# RF.net
KiCad netlist of a schematic drawn in Altium Designer
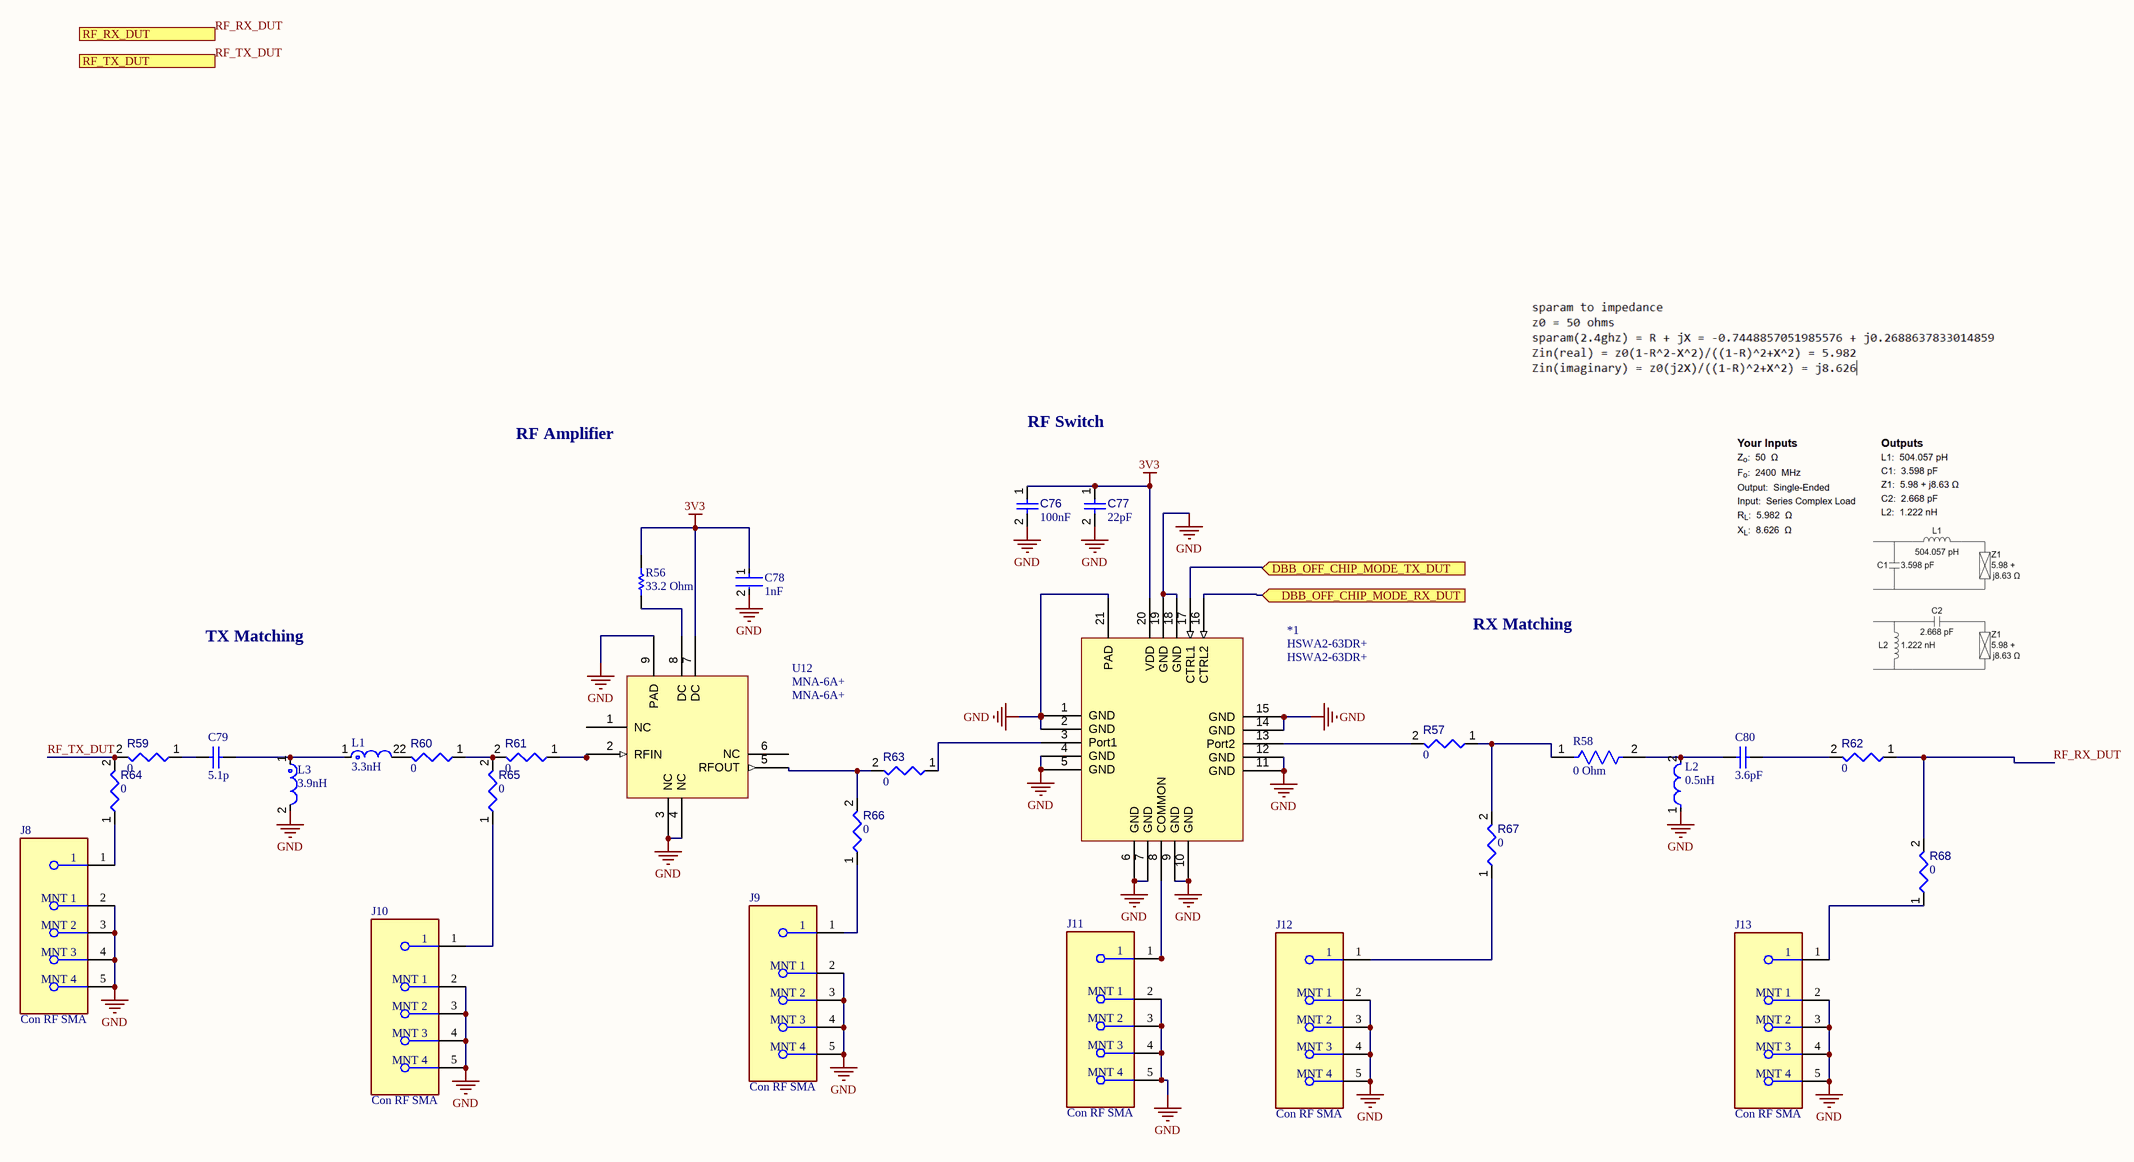
[diagram p0: RF.SchDoc]

(export (version "E")
  (design (tool "Eeschema 10.0.6"))
  (components
    (comp (ref "*1")
      (value "HSWA2-63DR+")
      (footprint "HSWA2-63DR+-Footprint-1")
      (description "Absorptive SPDT, SMT Solid State")
      (fields (field (name "U10") "HSWA2-63DR+") (field (name "MANUFACTURER") "Mini-Circuits"))
      (libsource (lib "EE194 Fall2022") (part "HSWA2-63DR+"))
    )
    (comp (ref "C76")
      (value "100nF")
      (footprint "CAPC1005X56X25LL10T15")
      (description "Chip Capacitor, 0.1 uF, +/- 5%, 16 V, 0402 (1005 Metric)")
      (fields (field (name "TOLERANCE") "5%") (field (name "Comment") "0.1uF"))
      (libsource (lib "EE194 Fall2022") (part "CAP-NP-2"))
    )
    (comp (ref "C77")
      (value "22pF")
      (footprint "CAPC0402(1005)60_L")
      (description "Chip Capacitor, 22pF +/-10%, 50V, 0402, Thickness 0.6 mm")
      (fields (field (name "TOLERANCE") "10%"))
      (libsource (lib "EE194 Fall2022") (part "CAP-NP-2"))
    )
    (comp (ref "C78")
      (value "1nF")
      (footprint "FP-CL10-IPC_C")
      (description "Cap Ceramic 1nF 50V X7R ±10% Pad SMD 0603 +125°C T/R")
      (fields (field (name "VOLTAGE") "50V") (field (name "TOLERANCE") "10%"))
      (libsource (lib "Altium Content Vault") (part "b4654b650e69147ec39a6b967a45e02"))
    )
    (comp (ref "C79")
      (value "5.1p")
      (footprint "CAPC1608X90X35NL15T15")
      (fields
        (field (name "PART NUMBER") "06031A5R1CAT2A")
        (field (name "MANUFACTURER") "AVX Interconnect / Elco")
      )
      (libsource (lib "Altium Content Vault") (part "CAP"))
    )
    (comp (ref "C80")
      (value "3.6pF")
      (footprint "CAPC1608X74X38LL10T13")
      (fields
        (field (name "MANUFACTURER") "AVX Interconnect / Elco")
        (field (name "PART NUMBER") "ML03V13R6BAT2A")
      )
      (libsource (lib "Altium Content Vault") (part "CAP"))
    )
    (comp (ref "J8")
      (value "Con RF SMA")
      (footprint "FP-RF2-04A-T-00-50-G-MFG")
      (description "CONN SMA JACK STR 50 OHM PCB")
      (libsource (lib "Altium Content Vault") (part "c65b8a639cdaef1819ea20b5466f8fa"))
    )
    (comp (ref "J9")
      (value "Con RF SMA")
      (footprint "FP-RF2-04A-T-00-50-G-MFG")
      (description "CONN SMA JACK STR 50 OHM PCB")
      (libsource (lib "Altium Content Vault") (part "c65b8a639cdaef1819ea20b5466f8fa"))
    )
    (comp (ref "J10")
      (value "Con RF SMA")
      (footprint "FP-RF2-04A-T-00-50-G-MFG")
      (description "CONN SMA JACK STR 50 OHM PCB")
      (libsource (lib "Altium Content Vault") (part "c65b8a639cdaef1819ea20b5466f8fa"))
    )
    (comp (ref "J11")
      (value "Con RF SMA")
      (footprint "FP-RF2-04A-T-00-50-G-MFG")
      (description "CONN SMA JACK STR 50 OHM PCB")
      (libsource (lib "Altium Content Vault") (part "c65b8a639cdaef1819ea20b5466f8fa"))
    )
    (comp (ref "J12")
      (value "Con RF SMA")
      (footprint "FP-RF2-04A-T-00-50-G-MFG")
      (description "CONN SMA JACK STR 50 OHM PCB")
      (libsource (lib "Altium Content Vault") (part "c65b8a639cdaef1819ea20b5466f8fa"))
    )
    (comp (ref "J13")
      (value "Con RF SMA")
      (footprint "FP-RF2-04A-T-00-50-G-MFG")
      (description "CONN SMA JACK STR 50 OHM PCB")
      (libsource (lib "Altium Content Vault") (part "c65b8a639cdaef1819ea20b5466f8fa"))
    )
    (comp (ref "L1")
      (value "3.3nH")
      (footprint "FP-LQG18HH_00-MFG")
      (description "Multilayer type RF Inductor 3.3nH ±0.3nH 0.12Ω 1000mA 0603")
      (libsource (lib "Altium Content Vault") (part "4cc4b267dca4c8e51f7102f422741d8"))
    )
    (comp (ref "L2")
      (value "0.5nH")
      (footprint "FP-LQW18AN_00-MFG")
      (description "Wire Wound RF Inductor 5.6nH ±0.5nH 750mA 0.082Ω 0603 (1608)")
      (libsource (lib "Altium Content Vault") (part "725321dda6339637d4d059423bc1c3c"))
    )
    (comp (ref "L3")
      (value "3.9nH")
      (footprint "FP-LQG18HH_00-MFG")
      (description "Multilayer type RF Inductor 3.9nH ±0.3nH 0.15Ω 900mA 0603")
      (libsource (lib "Altium Content Vault") (part "4cc4b267dca4c8e51f7102f422741d8"))
    )
    (comp (ref "R56")
      (value "33.2 Ohm")
      (footprint "RESC1608X55X25NL10T15")
      (fields (field (name "MANUFACTURER") "Yageo") (field (name "PART NUMBER") "RC0603FR-0733R2L"))
      (libsource (lib "Altium Content Vault") (part "RES"))
    )
    (comp (ref "R57")
      (value "0")
      (footprint "RESC0603(1608)_L")
      (description "Jumper 0603 (1608 Metric)")
      (fields (field (name "Comment") "0R3J"))
      (libsource (lib "EE194 Fall2022") (part "0R3J"))
    )
    (comp (ref "R58")
      (value "0 Ohm")
      (footprint "FP-CRCW0603-C-IPC_B")
      (description "RES 0 OHM JUMPER 1/10W 0603")
      (libsource (lib "Altium Content Vault") (part "1029c3af85768c4190bb7ad29bc67b5"))
    )
    (comp (ref "R59")
      (value "0")
      (footprint "RESC0603(1608)_L")
      (description "Jumper 0603 (1608 Metric)")
      (fields (field (name "Comment") "0R3J"))
      (libsource (lib "EE194 Fall2022") (part "0R3J"))
    )
    (comp (ref "R60")
      (value "0")
      (footprint "RESC0603(1608)_L")
      (description "Jumper 0603 (1608 Metric)")
      (fields (field (name "Comment") "0R3J"))
      (libsource (lib "EE194 Fall2022") (part "0R3J"))
    )
    (comp (ref "R61")
      (value "0")
      (footprint "RESC0603(1608)_L")
      (description "Jumper 0603 (1608 Metric)")
      (fields (field (name "Comment") "0R3J"))
      (libsource (lib "EE194 Fall2022") (part "0R3J"))
    )
    (comp (ref "R62")
      (value "0")
      (footprint "RESC0603(1608)_L")
      (description "Jumper 0603 (1608 Metric)")
      (fields (field (name "Comment") "0R3J"))
      (libsource (lib "EE194 Fall2022") (part "0R3J"))
    )
    (comp (ref "R63")
      (value "0")
      (footprint "RESC0603(1608)_L")
      (description "Jumper 0603 (1608 Metric)")
      (fields (field (name "Comment") "0R3J"))
      (libsource (lib "EE194 Fall2022") (part "0R3J"))
    )
    (comp (ref "R64")
      (value "0")
      (footprint "RESC0603(1608)_L")
      (description "Jumper 0603 (1608 Metric)")
      (fields (field (name "Comment") "0R3J"))
      (libsource (lib "EE194 Fall2022") (part "0R3J"))
    )
    (comp (ref "R65")
      (value "0")
      (footprint "RESC0603(1608)_L")
      (description "Jumper 0603 (1608 Metric)")
      (fields (field (name "Comment") "0R3J"))
      (libsource (lib "EE194 Fall2022") (part "0R3J"))
    )
    (comp (ref "R66")
      (value "0")
      (footprint "RESC0603(1608)_L")
      (description "Jumper 0603 (1608 Metric)")
      (fields (field (name "Comment") "0R3J"))
      (libsource (lib "EE194 Fall2022") (part "0R3J"))
    )
    (comp (ref "R67")
      (value "0")
      (footprint "RESC0603(1608)_L")
      (description "Jumper 0603 (1608 Metric)")
      (fields (field (name "Comment") "0R3J"))
      (libsource (lib "EE194 Fall2022") (part "0R3J"))
    )
    (comp (ref "R68")
      (value "0")
      (footprint "RESC0603(1608)_L")
      (description "Jumper 0603 (1608 Metric)")
      (fields (field (name "Comment") "0R3J"))
      (libsource (lib "EE194 Fall2022") (part "0R3J"))
    )
    (comp (ref "U12")
      (value "MNA-6A+")
      (footprint "MNA-6A+-Footprint-1")
      (description "RF Amp Single MMIC Amp 2.5GHz 5V 8-Pin Case DQ-849 T/R")
      (fields (field (name "U11") "MNA-6A+") (field (name "MANUFACTURER") "Mini-Circuits"))
      (libsource (lib "EE194 Fall2022") (part "MNA-6A+"))
    )
  )
  (nets
    (net (code "1") (name "/DBB_OFF_CHIP_MODE_RX_DUT") (class "Default")
      (node (ref "*1") (pin "16") (pinfunction "CTRL2_16") (pintype "input"))
    )
    (net (code "2") (name "/DBB_OFF_CHIP_MODE_TX_DUT") (class "Default")
      (node (ref "*1") (pin "17") (pinfunction "CTRL1_17") (pintype "input"))
    )
    (net (code "3") (name "/RF_RX_DUT") (class "Default")
      (node (ref "R62") (pin "1") (pinfunction "1_1") (pintype "passive"))
      (node (ref "R68") (pin "2") (pinfunction "2_2") (pintype "passive"))
    )
    (net (code "4") (name "/RF_TX_DUT") (class "Default")
      (node (ref "R59") (pin "2") (pinfunction "2_2") (pintype "passive"))
      (node (ref "R64") (pin "2") (pinfunction "2_2") (pintype "passive"))
    )
    (net (code "5") (name "3V3") (class "Default")
      (node (ref "*1") (pin "20") (pinfunction "VDD_20") (pintype "passive"))
      (node (ref "C76") (pin "1") (pinfunction "1_1") (pintype "passive"))
      (node (ref "C77") (pin "1") (pinfunction "1_1") (pintype "passive"))
      (node (ref "C78") (pin "1") (pinfunction "1_1") (pintype "passive"))
      (node (ref "R56") (pin "2") (pinfunction "2_2") (pintype "passive"))
      (node (ref "U12") (pin "7") (pinfunction "DC_7") (pintype "passive"))
    )
    (net (code "6") (name "GND") (class "Default")
      (node (ref "*1") (pin "1") (pinfunction "GND_1") (pintype "passive"))
      (node (ref "*1") (pin "10") (pinfunction "GND_10") (pintype "passive"))
      (node (ref "*1") (pin "11") (pinfunction "GND_11") (pintype "passive"))
      (node (ref "*1") (pin "12") (pinfunction "GND_12") (pintype "passive"))
      (node (ref "*1") (pin "14") (pinfunction "GND_14") (pintype "passive"))
      (node (ref "*1") (pin "15") (pinfunction "GND_15") (pintype "passive"))
      (node (ref "*1") (pin "18") (pinfunction "GND_18") (pintype "passive"))
      (node (ref "*1") (pin "19") (pinfunction "GND_19") (pintype "passive"))
      (node (ref "*1") (pin "2") (pinfunction "GND_2") (pintype "passive"))
      (node (ref "*1") (pin "21") (pinfunction "PAD_21") (pintype "passive"))
      (node (ref "*1") (pin "4") (pinfunction "GND_4") (pintype "passive"))
      (node (ref "*1") (pin "5") (pinfunction "GND_5") (pintype "passive"))
      (node (ref "*1") (pin "6") (pinfunction "GND_6") (pintype "passive"))
      (node (ref "*1") (pin "7") (pinfunction "GND_7") (pintype "passive"))
      (node (ref "*1") (pin "9") (pinfunction "GND_9") (pintype "passive"))
      (node (ref "C76") (pin "2") (pinfunction "2_2") (pintype "passive"))
      (node (ref "C77") (pin "2") (pinfunction "2_2") (pintype "passive"))
      (node (ref "C78") (pin "2") (pinfunction "2_2") (pintype "passive"))
      (node (ref "J10") (pin "2") (pinfunction "MNT_1_2") (pintype "passive"))
      (node (ref "J10") (pin "3") (pinfunction "MNT_2_3") (pintype "passive"))
      (node (ref "J10") (pin "4") (pinfunction "MNT_3_4") (pintype "passive"))
      (node (ref "J10") (pin "5") (pinfunction "MNT_4_5") (pintype "passive"))
      (node (ref "J11") (pin "2") (pinfunction "MNT_1_2") (pintype "passive"))
      (node (ref "J11") (pin "3") (pinfunction "MNT_2_3") (pintype "passive"))
      (node (ref "J11") (pin "4") (pinfunction "MNT_3_4") (pintype "passive"))
      (node (ref "J11") (pin "5") (pinfunction "MNT_4_5") (pintype "passive"))
      (node (ref "J12") (pin "2") (pinfunction "MNT_1_2") (pintype "passive"))
      (node (ref "J12") (pin "3") (pinfunction "MNT_2_3") (pintype "passive"))
      (node (ref "J12") (pin "4") (pinfunction "MNT_3_4") (pintype "passive"))
      (node (ref "J12") (pin "5") (pinfunction "MNT_4_5") (pintype "passive"))
      (node (ref "J13") (pin "2") (pinfunction "MNT_1_2") (pintype "passive"))
      (node (ref "J13") (pin "3") (pinfunction "MNT_2_3") (pintype "passive"))
      (node (ref "J13") (pin "4") (pinfunction "MNT_3_4") (pintype "passive"))
      (node (ref "J13") (pin "5") (pinfunction "MNT_4_5") (pintype "passive"))
      (node (ref "J8") (pin "2") (pinfunction "MNT_1_2") (pintype "passive"))
      (node (ref "J8") (pin "3") (pinfunction "MNT_2_3") (pintype "passive"))
      (node (ref "J8") (pin "4") (pinfunction "MNT_3_4") (pintype "passive"))
      (node (ref "J8") (pin "5") (pinfunction "MNT_4_5") (pintype "passive"))
      (node (ref "J9") (pin "2") (pinfunction "MNT_1_2") (pintype "passive"))
      (node (ref "J9") (pin "3") (pinfunction "MNT_2_3") (pintype "passive"))
      (node (ref "J9") (pin "4") (pinfunction "MNT_3_4") (pintype "passive"))
      (node (ref "J9") (pin "5") (pinfunction "MNT_4_5") (pintype "passive"))
      (node (ref "L2") (pin "1") (pinfunction "1_1") (pintype "passive"))
      (node (ref "L3") (pin "2") (pinfunction "2_2") (pintype "passive"))
      (node (ref "U12") (pin "3") (pinfunction "NC_3") (pintype "passive"))
      (node (ref "U12") (pin "4") (pinfunction "NC_4") (pintype "passive"))
      (node (ref "U12") (pin "9") (pinfunction "PAD_9") (pintype "passive"))
    )
    (net (code "7") (name "Net-(*1-COMMON)") (class "Default")
      (node (ref "*1") (pin "8") (pinfunction "COMMON_8") (pintype "passive"))
      (node (ref "J11") (pin "1") (pinfunction "1_1") (pintype "passive"))
    )
    (net (code "8") (name "Net-(*1-Port1)") (class "Default")
      (node (ref "*1") (pin "3") (pinfunction "Port1_3") (pintype "passive"))
      (node (ref "R63") (pin "1") (pinfunction "1_1") (pintype "passive"))
    )
    (net (code "9") (name "Net-(*1-Port2)") (class "Default")
      (node (ref "*1") (pin "13") (pinfunction "Port2_13") (pintype "passive"))
      (node (ref "R57") (pin "2") (pinfunction "2_2") (pintype "passive"))
    )
    (net (code "10") (name "Net-(C79-Pad1)") (class "Default")
      (node (ref "C79") (pin "1") (pinfunction "1_1") (pintype "passive"))
      (node (ref "R59") (pin "1") (pinfunction "1_1") (pintype "passive"))
    )
    (net (code "11") (name "Net-(C79-Pad2)") (class "Default")
      (node (ref "C79") (pin "2") (pinfunction "2_2") (pintype "passive"))
      (node (ref "L1") (pin "1") (pinfunction "1_1") (pintype "passive"))
      (node (ref "L3") (pin "1") (pinfunction "1_1") (pintype "passive"))
    )
    (net (code "12") (name "Net-(C80-Pad1)") (class "Default")
      (node (ref "C80") (pin "1") (pinfunction "1_1") (pintype "passive"))
      (node (ref "L2") (pin "2") (pinfunction "2_2") (pintype "passive"))
      (node (ref "R58") (pin "2") (pinfunction "2_2") (pintype "passive"))
    )
    (net (code "13") (name "Net-(C80-Pad2)") (class "Default")
      (node (ref "C80") (pin "2") (pinfunction "2_2") (pintype "passive"))
      (node (ref "R62") (pin "2") (pinfunction "2_2") (pintype "passive"))
    )
    (net (code "14") (name "Net-(J8-Pad1)") (class "Default")
      (node (ref "J8") (pin "1") (pinfunction "1_1") (pintype "passive"))
      (node (ref "R64") (pin "1") (pinfunction "1_1") (pintype "passive"))
    )
    (net (code "15") (name "Net-(J9-Pad1)") (class "Default")
      (node (ref "J9") (pin "1") (pinfunction "1_1") (pintype "passive"))
      (node (ref "R66") (pin "1") (pinfunction "1_1") (pintype "passive"))
    )
    (net (code "16") (name "Net-(J10-Pad1)") (class "Default")
      (node (ref "J10") (pin "1") (pinfunction "1_1") (pintype "passive"))
      (node (ref "R65") (pin "1") (pinfunction "1_1") (pintype "passive"))
    )
    (net (code "17") (name "Net-(J12-Pad1)") (class "Default")
      (node (ref "J12") (pin "1") (pinfunction "1_1") (pintype "passive"))
      (node (ref "R67") (pin "1") (pinfunction "1_1") (pintype "passive"))
    )
    (net (code "18") (name "Net-(J13-Pad1)") (class "Default")
      (node (ref "J13") (pin "1") (pinfunction "1_1") (pintype "passive"))
      (node (ref "R68") (pin "1") (pinfunction "1_1") (pintype "passive"))
    )
    (net (code "19") (name "Net-(L1-Pad2)") (class "Default")
      (node (ref "L1") (pin "2") (pinfunction "2_2") (pintype "passive"))
      (node (ref "R60") (pin "2") (pinfunction "2_2") (pintype "passive"))
    )
    (net (code "20") (name "Net-(R56-Pad1)") (class "Default")
      (node (ref "R56") (pin "1") (pinfunction "1_1") (pintype "passive"))
      (node (ref "U12") (pin "8") (pinfunction "DC_8") (pintype "passive"))
    )
    (net (code "21") (name "Net-(R57-Pad1)") (class "Default")
      (node (ref "R57") (pin "1") (pinfunction "1_1") (pintype "passive"))
      (node (ref "R58") (pin "1") (pinfunction "1_1") (pintype "passive"))
      (node (ref "R67") (pin "2") (pinfunction "2_2") (pintype "passive"))
    )
    (net (code "22") (name "Net-(R60-Pad1)") (class "Default")
      (node (ref "R60") (pin "1") (pinfunction "1_1") (pintype "passive"))
      (node (ref "R61") (pin "2") (pinfunction "2_2") (pintype "passive"))
      (node (ref "R65") (pin "2") (pinfunction "2_2") (pintype "passive"))
    )
    (net (code "23") (name "Net-(U12-RFIN)") (class "Default")
      (node (ref "R61") (pin "1") (pinfunction "1_1") (pintype "passive"))
      (node (ref "U12") (pin "2") (pinfunction "RFIN_2") (pintype "input"))
    )
    (net (code "24") (name "Net-(U12-RFOUT)") (class "Default")
      (node (ref "R63") (pin "2") (pinfunction "2_2") (pintype "passive"))
      (node (ref "R66") (pin "2") (pinfunction "2_2") (pintype "passive"))
      (node (ref "U12") (pin "5") (pinfunction "RFOUT_5") (pintype "output"))
    )
    (net (code "25") (name "unconnected-(U12-NC-Pad1)") (class "Default")
      (node (ref "U12") (pin "1") (pinfunction "NC_1") (pintype "passive"))
    )
    (net (code "26") (name "unconnected-(U12-NC-Pad6)") (class "Default")
      (node (ref "U12") (pin "6") (pinfunction "NC_6") (pintype "passive"))
    )
  )
)
